# 07_EXPANSION.net
KiCad netlist of a schematic drawn in Altium Designer
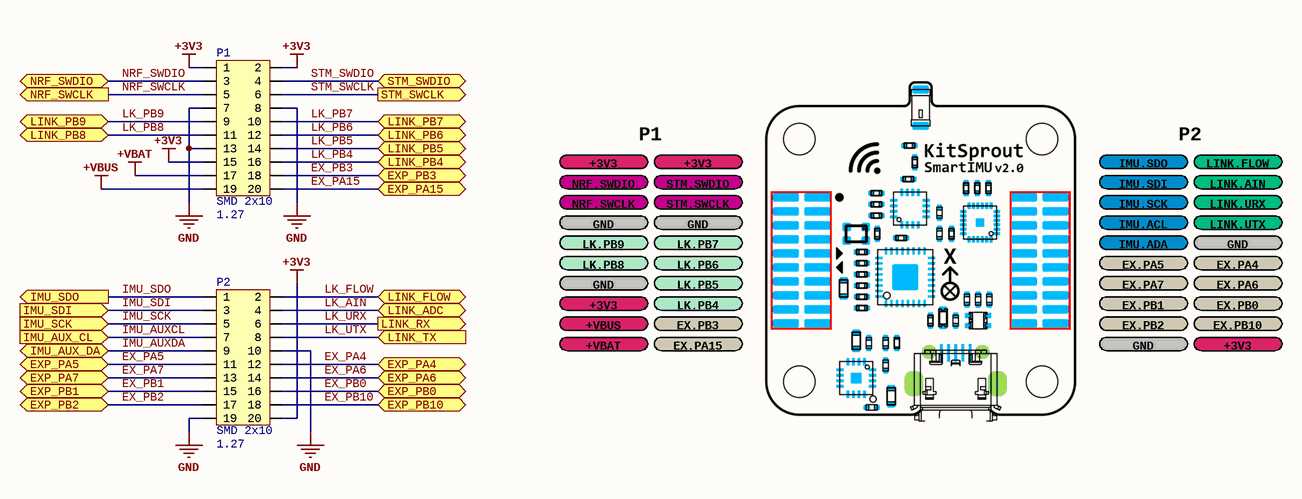
[diagram p0: [07] EXPANSION.SchDoc]

(export (version "E")
  (design (tool "Eeschema 10.0.6"))
  (components
    (comp (ref "P1")
      (value "1.27")
      (footprint "PCB_ConnectorHDR:HDR2X10_1.27_180TBH")
      (description "Header")
      (fields (field (name "TYPE") "SMD 2x10"))
      (libsource (lib "SCH_ConnectorHDR") (part "HDR2x10_1.27"))
    )
    (comp (ref "P2")
      (value "1.27")
      (footprint "PCB_ConnectorHDR:HDR2X10_1.27_180TBH")
      (description "Header")
      (fields (field (name "TYPE") "SMD 2x10"))
      (libsource (lib "SCH_ConnectorHDR") (part "HDR2x10_1.27"))
    )
  )
  (nets
    (net (code "1") (name "+3V3") (class "Default")
      (node (ref "P1") (pin "1") (pinfunction "1_1") (pintype "passive"))
      (node (ref "P1") (pin "15") (pinfunction "15_15") (pintype "passive"))
      (node (ref "P1") (pin "2") (pinfunction "2_2") (pintype "passive"))
      (node (ref "P2") (pin "20") (pinfunction "20_20") (pintype "passive"))
    )
    (net (code "2") (name "+VBAT") (class "Default")
      (node (ref "P1") (pin "17") (pinfunction "17_17") (pintype "passive"))
    )
    (net (code "3") (name "+VBUS") (class "Default")
      (node (ref "P1") (pin "19") (pinfunction "19_19") (pintype "passive"))
    )
    (net (code "4") (name "/EX_PA4") (class "Default")
      (node (ref "P2") (pin "12") (pinfunction "12_12") (pintype "passive"))
    )
    (net (code "5") (name "/EX_PA5") (class "Default")
      (node (ref "P2") (pin "11") (pinfunction "11_11") (pintype "passive"))
    )
    (net (code "6") (name "/EX_PA6") (class "Default")
      (node (ref "P2") (pin "14") (pinfunction "14_14") (pintype "passive"))
    )
    (net (code "7") (name "/EX_PA7") (class "Default")
      (node (ref "P2") (pin "13") (pinfunction "13_13") (pintype "passive"))
    )
    (net (code "8") (name "/EX_PA15") (class "Default")
      (node (ref "P1") (pin "20") (pinfunction "20_20") (pintype "passive"))
    )
    (net (code "9") (name "/EX_PB0") (class "Default")
      (node (ref "P2") (pin "16") (pinfunction "16_16") (pintype "passive"))
    )
    (net (code "10") (name "/EX_PB1") (class "Default")
      (node (ref "P2") (pin "15") (pinfunction "15_15") (pintype "passive"))
    )
    (net (code "11") (name "/EX_PB2") (class "Default")
      (node (ref "P2") (pin "17") (pinfunction "17_17") (pintype "passive"))
    )
    (net (code "12") (name "/EX_PB3") (class "Default")
      (node (ref "P1") (pin "18") (pinfunction "18_18") (pintype "passive"))
    )
    (net (code "13") (name "/EX_PB10") (class "Default")
      (node (ref "P2") (pin "18") (pinfunction "18_18") (pintype "passive"))
    )
    (net (code "14") (name "/IMU_AUXCL") (class "Default")
      (node (ref "P2") (pin "7") (pinfunction "7_7") (pintype "passive"))
    )
    (net (code "15") (name "/IMU_AUXDA") (class "Default")
      (node (ref "P2") (pin "9") (pinfunction "9_9") (pintype "passive"))
    )
    (net (code "16") (name "/IMU_SCK") (class "Default")
      (node (ref "P2") (pin "5") (pinfunction "5_5") (pintype "passive"))
    )
    (net (code "17") (name "/IMU_SDI") (class "Default")
      (node (ref "P2") (pin "3") (pinfunction "3_3") (pintype "passive"))
    )
    (net (code "18") (name "/IMU_SDO") (class "Default")
      (node (ref "P2") (pin "1") (pinfunction "1_1") (pintype "passive"))
    )
    (net (code "19") (name "/LK_AIN") (class "Default")
      (node (ref "P2") (pin "4") (pinfunction "4_4") (pintype "passive"))
    )
    (net (code "20") (name "/LK_FLOW") (class "Default")
      (node (ref "P2") (pin "2") (pinfunction "2_2") (pintype "passive"))
    )
    (net (code "21") (name "/LK_PB4") (class "Default")
      (node (ref "P1") (pin "16") (pinfunction "16_16") (pintype "passive"))
    )
    (net (code "22") (name "/LK_PB5") (class "Default")
      (node (ref "P1") (pin "14") (pinfunction "14_14") (pintype "passive"))
    )
    (net (code "23") (name "/LK_PB6") (class "Default")
      (node (ref "P1") (pin "12") (pinfunction "12_12") (pintype "passive"))
    )
    (net (code "24") (name "/LK_PB7") (class "Default")
      (node (ref "P1") (pin "10") (pinfunction "10_10") (pintype "passive"))
    )
    (net (code "25") (name "/LK_PB8") (class "Default")
      (node (ref "P1") (pin "11") (pinfunction "11_11") (pintype "passive"))
    )
    (net (code "26") (name "/LK_PB9") (class "Default")
      (node (ref "P1") (pin "9") (pinfunction "9_9") (pintype "passive"))
    )
    (net (code "27") (name "/LK_URX") (class "Default")
      (node (ref "P2") (pin "6") (pinfunction "6_6") (pintype "passive"))
    )
    (net (code "28") (name "/LK_UTX") (class "Default")
      (node (ref "P2") (pin "8") (pinfunction "8_8") (pintype "passive"))
    )
    (net (code "29") (name "/NRF_SWCLK") (class "Default")
      (node (ref "P1") (pin "5") (pinfunction "5_5") (pintype "passive"))
    )
    (net (code "30") (name "/NRF_SWDIO") (class "Default")
      (node (ref "P1") (pin "3") (pinfunction "3_3") (pintype "passive"))
    )
    (net (code "31") (name "/STM_SWCLK") (class "Default")
      (node (ref "P1") (pin "6") (pinfunction "6_6") (pintype "passive"))
    )
    (net (code "32") (name "/STM_SWDIO") (class "Default")
      (node (ref "P1") (pin "4") (pinfunction "4_4") (pintype "passive"))
    )
    (net (code "33") (name "GND") (class "Default")
      (node (ref "P1") (pin "13") (pinfunction "13_13") (pintype "passive"))
      (node (ref "P1") (pin "7") (pinfunction "7_7") (pintype "passive"))
      (node (ref "P1") (pin "8") (pinfunction "8_8") (pintype "passive"))
      (node (ref "P2") (pin "10") (pinfunction "10_10") (pintype "passive"))
      (node (ref "P2") (pin "19") (pinfunction "19_19") (pintype "passive"))
    )
  )
)
